# SCH_CapibaraZero_PCB_2024-12-05.net
KiCad netlist of a schematic drawn in EasyEDA
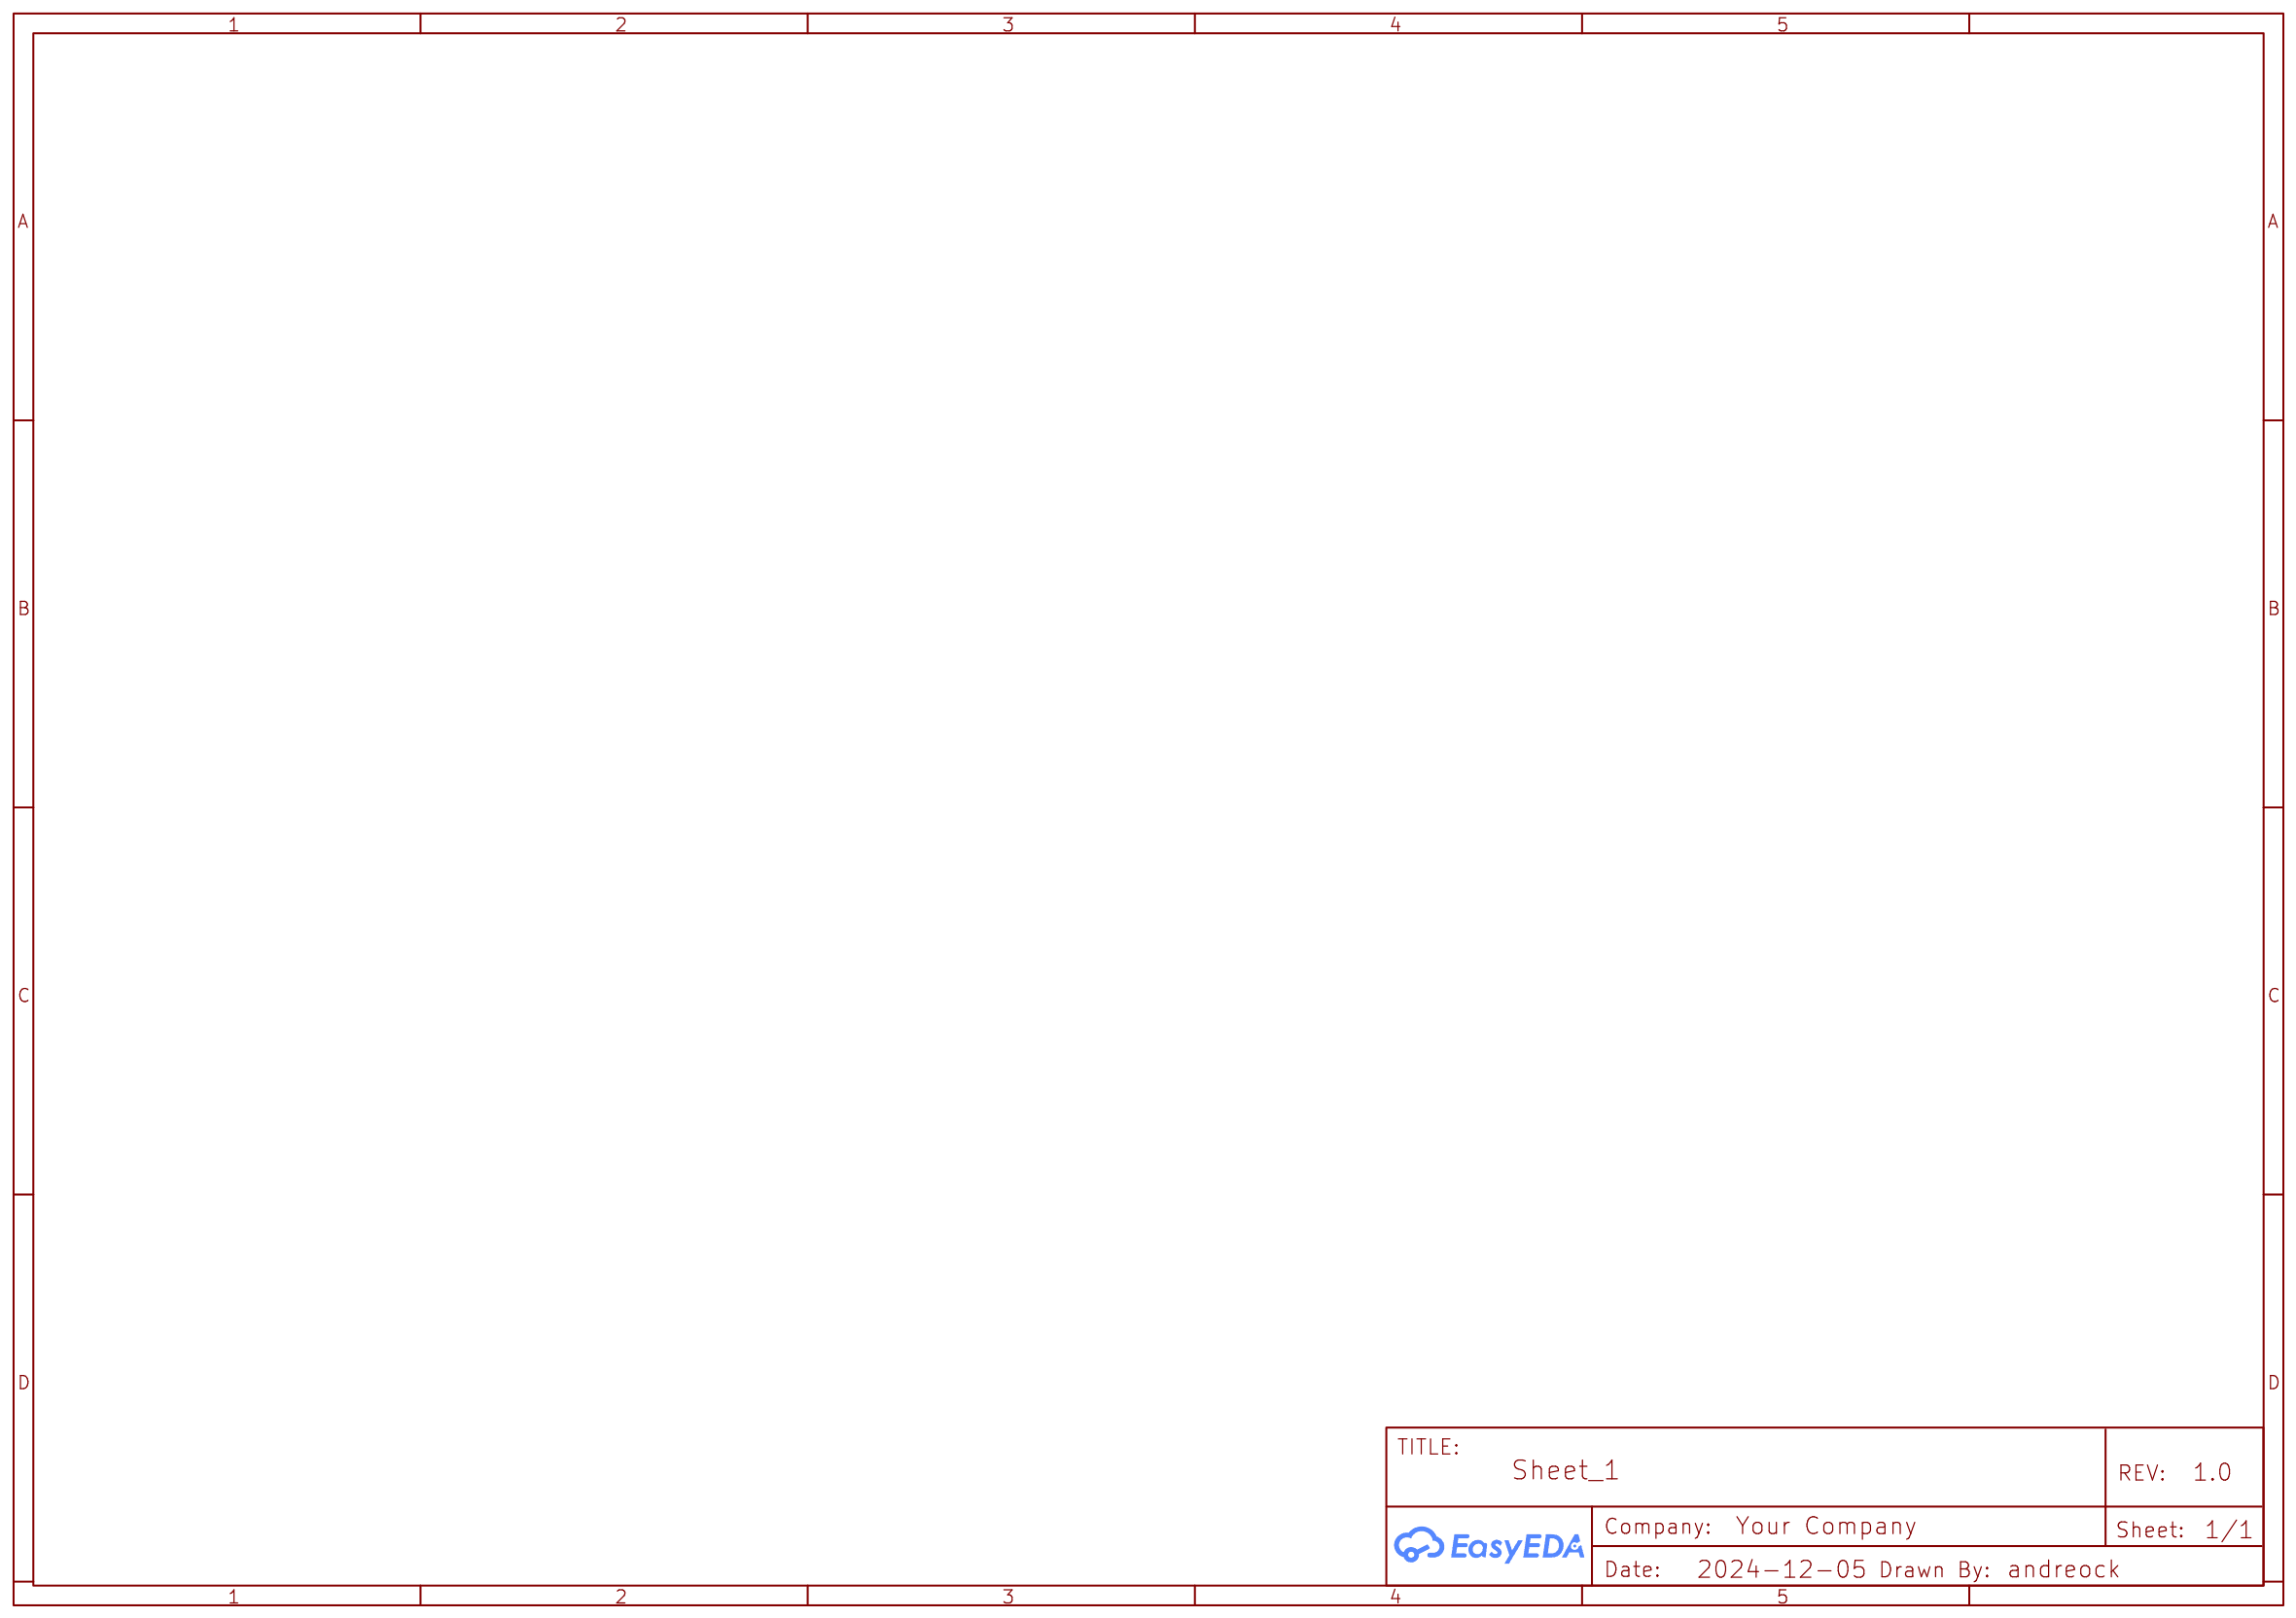
[diagram p0: Sheet_1]
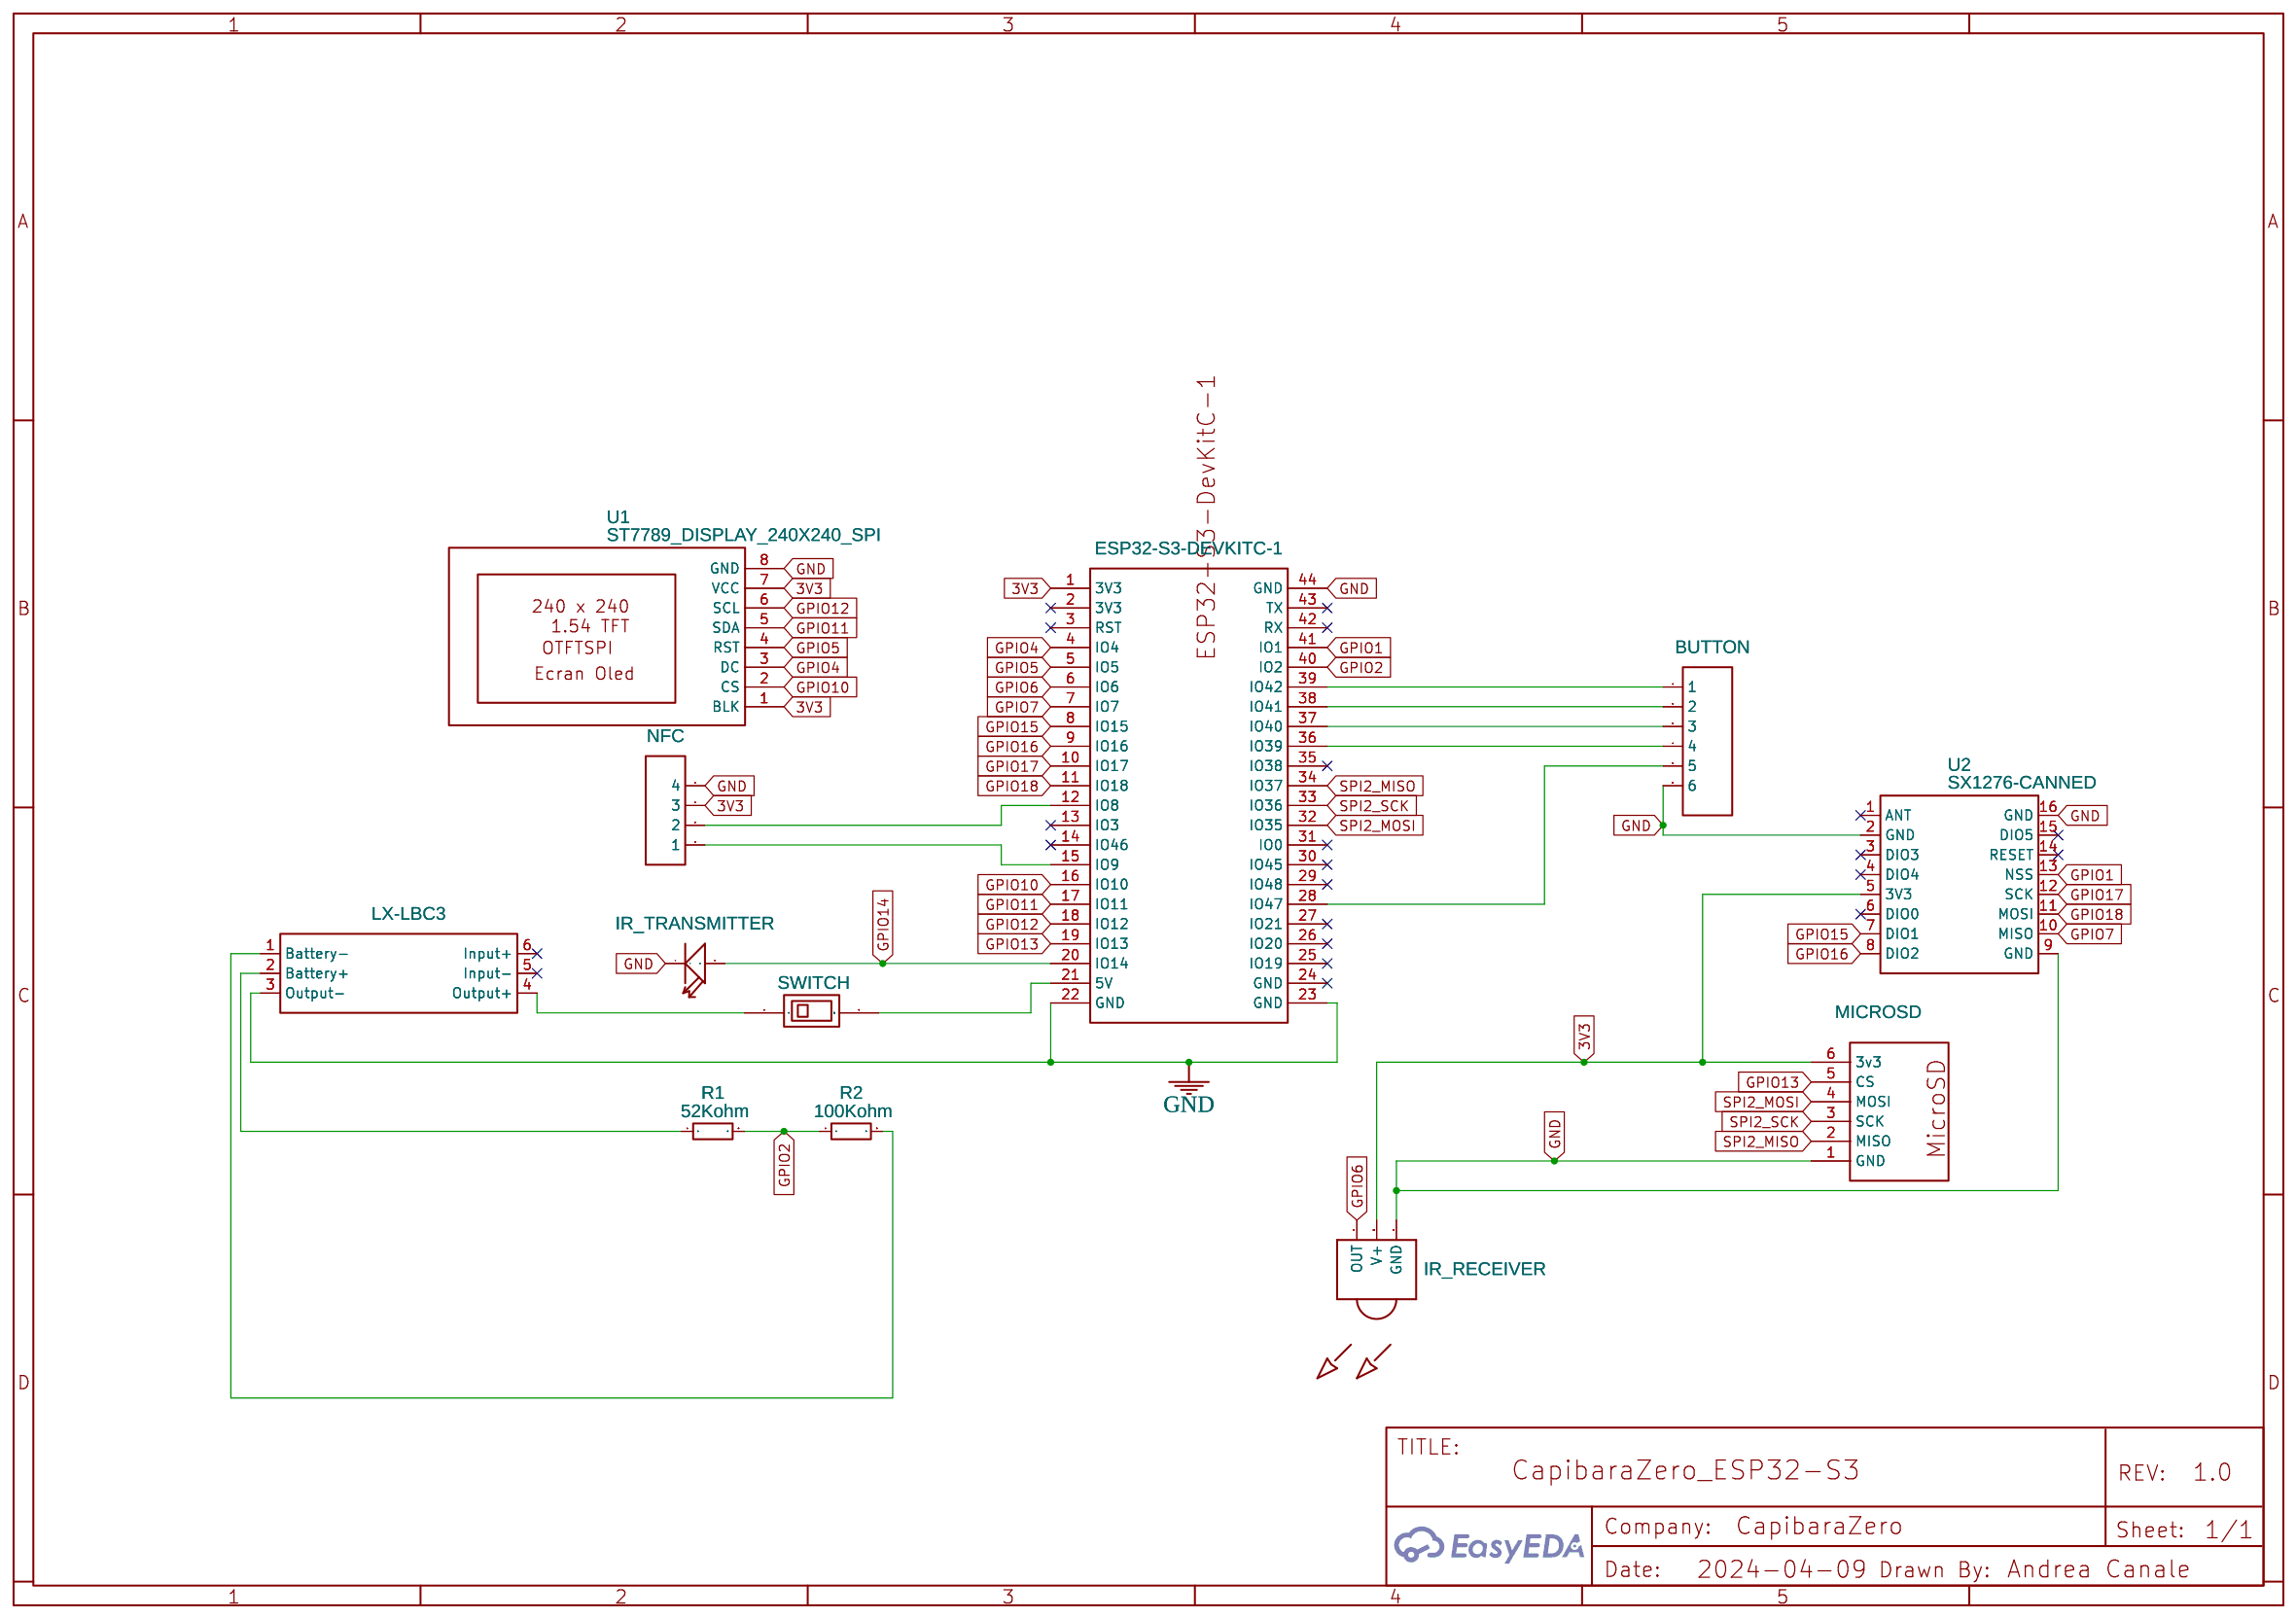
[diagram p1: CapibaraZero_Main_Scheme]
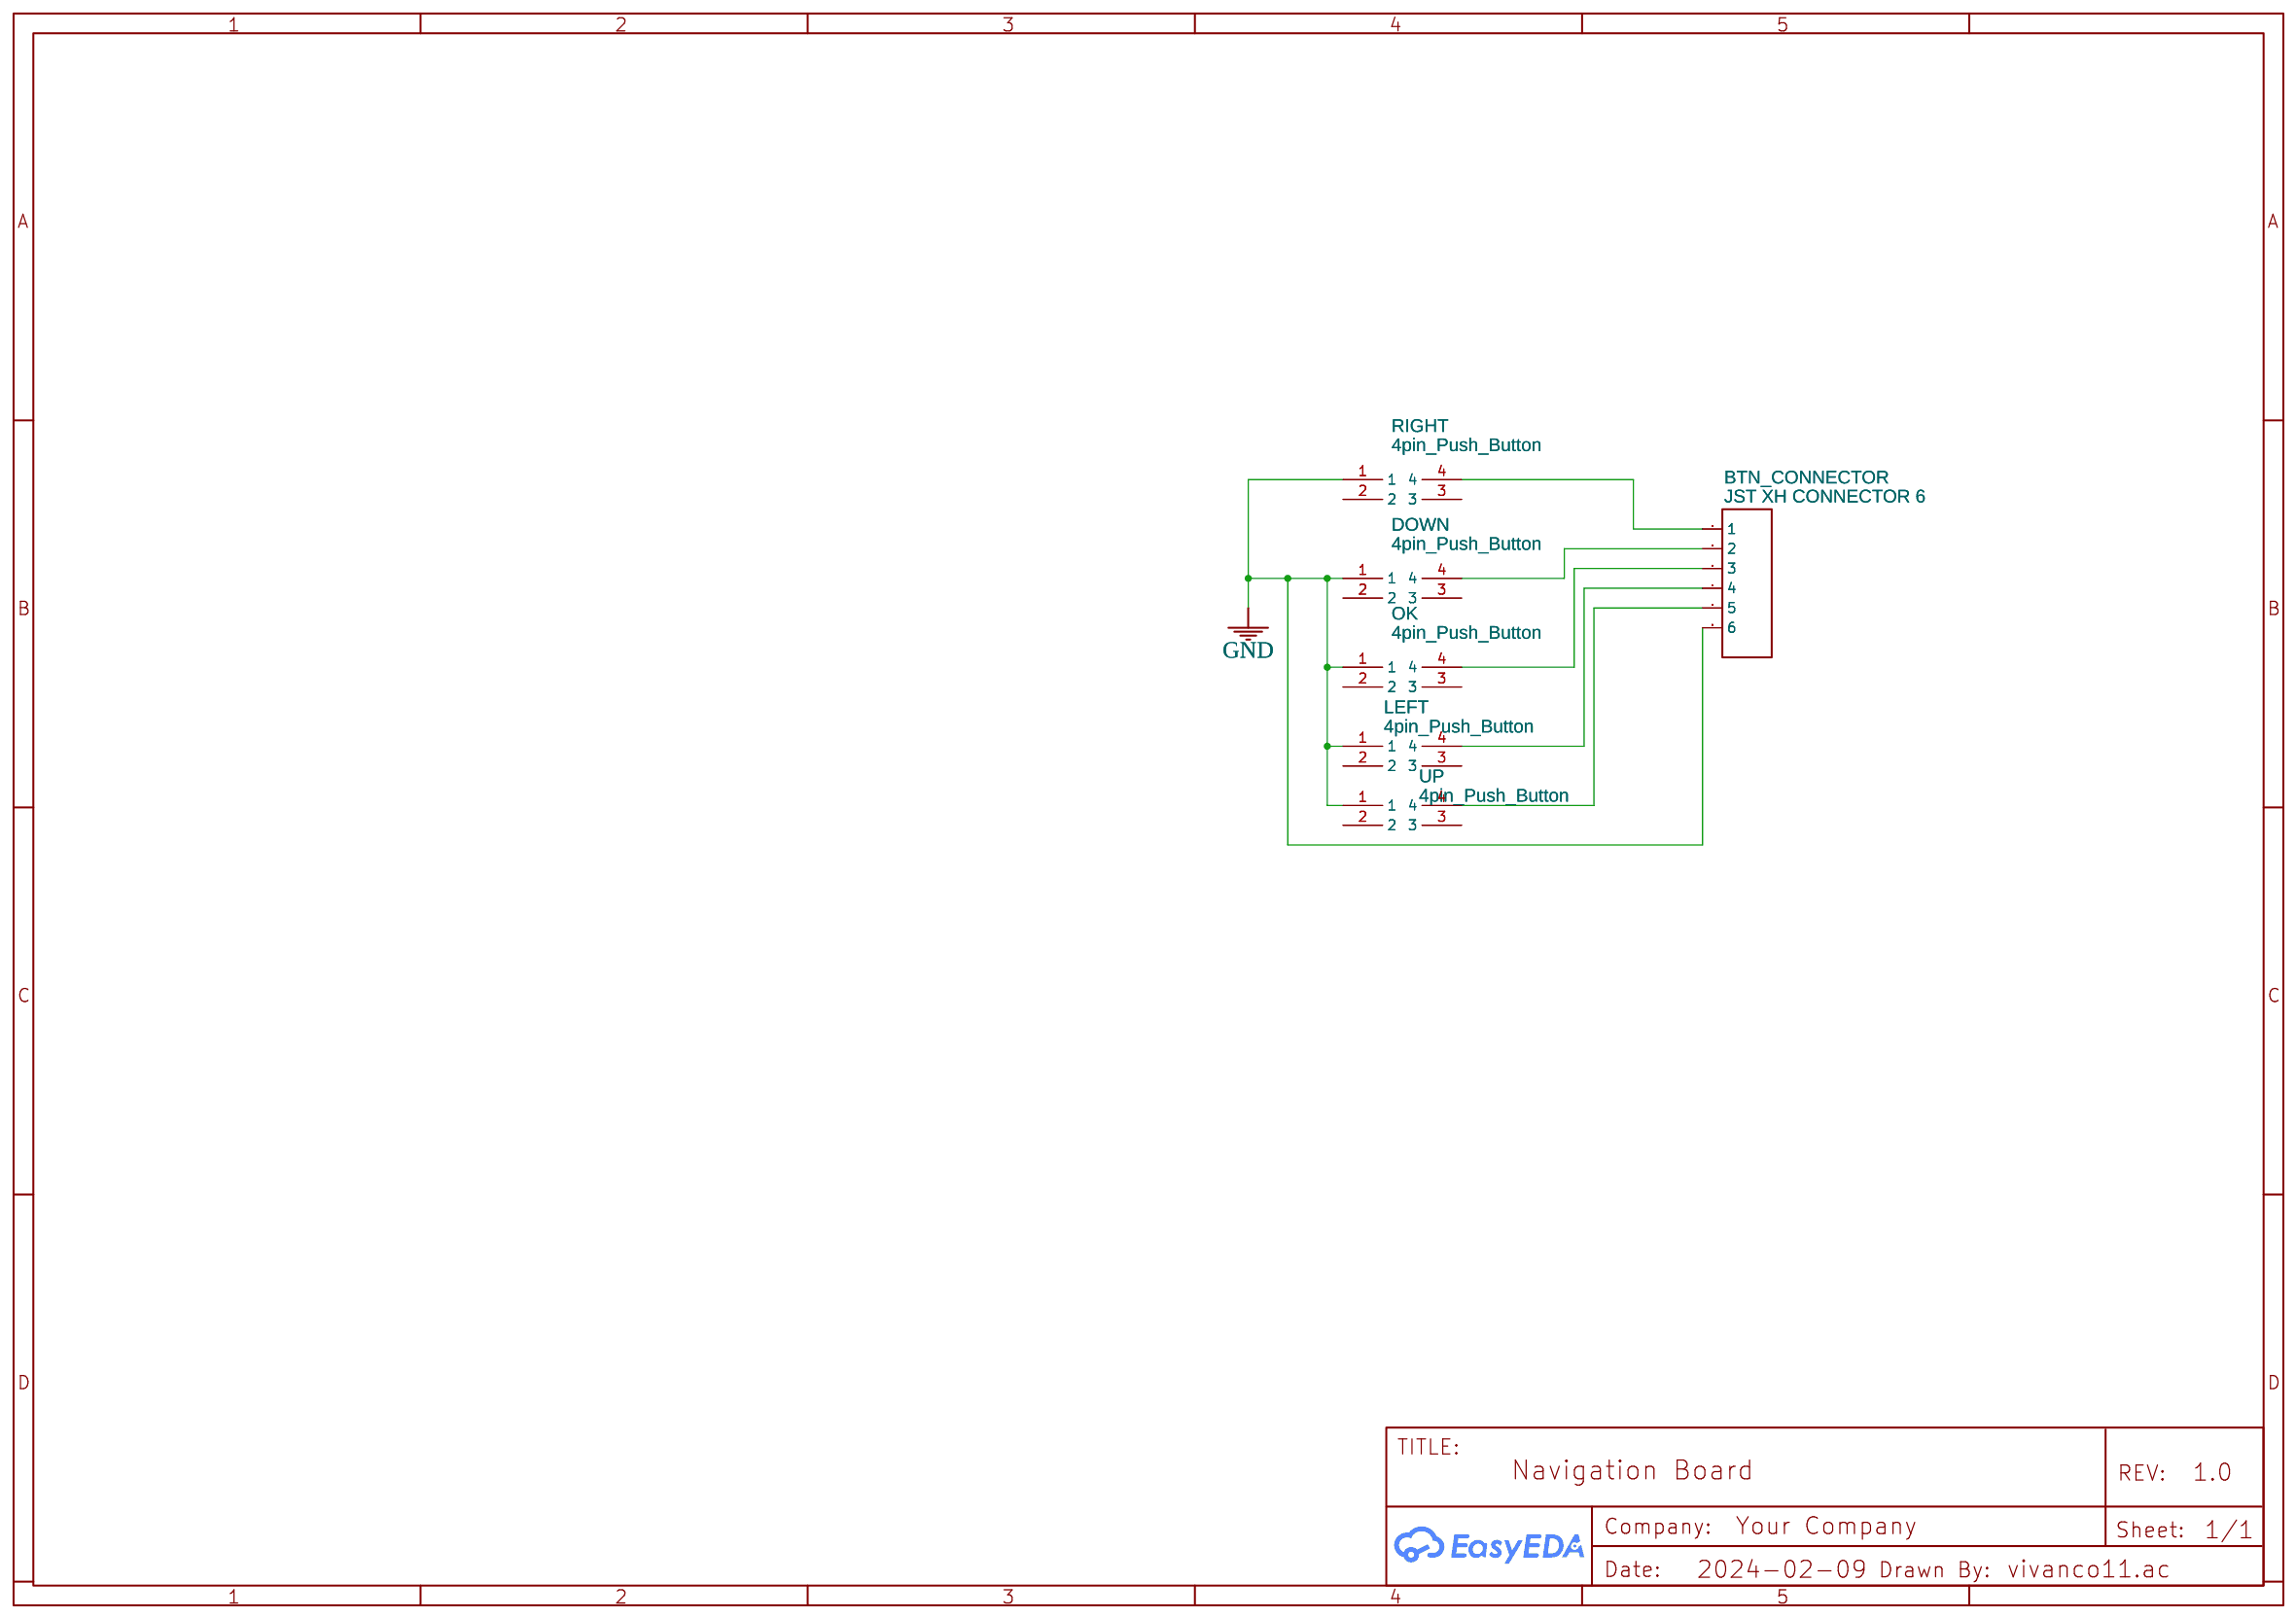
[diagram p2: Navigation board]

(export (version "E")
  (design (tool "Eeschema 10.0.6"))
  (components
    (comp (ref "BUTTON")
      (value "BTN Connector")
      (fields (field (name "Manufacturer Part") "JST_XH CONNECTOR"))
      (libsource (lib "") (part "JST XH CONNECTOR 6"))
    )
    (comp (ref "ESP32-S3-DEVKITC-1")
      (value "ESP32-S3-DevKitC-1 development board")
      (fields (field (name "Manufacturer") "Espressif"))
      (libsource (lib "") (part "ESP32-S3-DevKitC-1 development board"))
    )
    (comp (ref "IR_RECEIVER") (value "IR RECEIVER") (libsource (lib "") (part "IR TRANSMITTER")))
    (comp (ref "IR_TRANSMITTER")
      (value "DIP-IR-LED-940NM(2P-D5MM)")
      (fields (field (name "Manufacturer Part") "IR523B-W60W1"))
      (libsource (lib "") (part "DIP-IR-LED-940NM(2P-D5MM)"))
    )
    (comp (ref "LX-LBC3") (value "LX-LBC3") (libsource (lib "") (part "LX-LBC3")))
    (comp (ref "MICROSD") (value "MicroSDSPI") (libsource (lib "") (part "MicroSDSPI")))
    (comp (ref "NFC")
      (value "NFC Connector")
      (fields (field (name "Manufacturer Part") "JST_XH CONNECTOR"))
      (libsource (lib "") (part "JST XH CONNECTOR 4"))
    )
    (comp (ref "R1")
      (value "52Kohm")
      (fields
        (field (name "Manufacturer Part") "EWWR0001J20R0T9")
        (field (name "Manufacturer") "ResistorToday")
      )
      (libsource (lib "") (part "Resistor Normal"))
    )
    (comp (ref "R2")
      (value "100Kohm")
      (fields
        (field (name "Manufacturer Part") "EWWR0001J20R0T9")
        (field (name "Manufacturer") "ResistorToday")
      )
      (libsource (lib "") (part "Resistor Normal"))
    )
    (comp (ref "SWITCH") (value "1 Pole DIP switch") (libsource (lib "") (part "1 Pole DIP switch")))
    (comp (ref "U1")
      (value "ST7789_DISPLAY_240X240_SPI")
      (libsource (lib "") (part "ST7789_DISPLAY_240X240_SPI"))
    )
    (comp (ref "U2")
      (value "SX1276-CANNED")
      (fields (field (name "Manufacturer Part") "LoRa1276-C1") (field (name "Manufacturer") "G-NiceRF"))
      (libsource (lib "") (part "SX1276-CANNED"))
    )
    (comp (ref "BTN_CONNECTOR")
      (value "JST XH CONNECTOR 6")
      (fields (field (name "Manufacturer Part") "JST_XH CONNECTOR"))
      (libsource (lib "") (part "JST XH CONNECTOR 6"))
    )
    (comp (ref "DOWN") (value "4pin_Push_Button") (libsource (lib "") (part "4pin_Push_Button_3")))
    (comp (ref "LEFT") (value "4pin_Push_Button") (libsource (lib "") (part "4pin_Push_Button")))
    (comp (ref "OK") (value "4pin_Push_Button") (libsource (lib "") (part "4pin_Push_Button_4")))
    (comp (ref "RIGHT") (value "4pin_Push_Button") (libsource (lib "") (part "4pin_Push_Button_2")))
    (comp (ref "UP") (value "4pin_Push_Button") (libsource (lib "") (part "4pin_Push_Button_1")))
  )
  (nets
    (net (code "1") (name "3V3") (class "Default")
      (node (ref "ESP32-S3-DEVKITC-1") (pin "1") (pinfunction "3V3_1") (pintype "unspecified"))
      (node (ref "IR_RECEIVER") (pin "VCC") (pinfunction "V+_VCC") (pintype "unspecified"))
      (node (ref "MICROSD") (pin "6") (pinfunction "3v3_6") (pintype "unspecified"))
      (node (ref "NFC") (pin "3") (pinfunction "3_3") (pintype "unspecified"))
      (node (ref "U1") (pin "1") (pinfunction "BLK_1") (pintype "unspecified"))
      (node (ref "U1") (pin "7") (pinfunction "VCC_7") (pintype "unspecified"))
      (node (ref "U2") (pin "5") (pinfunction "3V3_5") (pintype "unspecified"))
    )
    (net (code "2") (name "GND") (class "Default")
      (node (ref "BTN_CONNECTOR") (pin "6") (pinfunction "6_6") (pintype "unspecified"))
      (node (ref "BUTTON") (pin "6") (pinfunction "6_6") (pintype "unspecified"))
      (node (ref "DOWN") (pin "1") (pinfunction "1_1") (pintype "unspecified"))
      (node (ref "ESP32-S3-DEVKITC-1") (pin "22") (pinfunction "GND_22") (pintype "unspecified"))
      (node (ref "ESP32-S3-DEVKITC-1") (pin "23") (pinfunction "GND_23") (pintype "unspecified"))
      (node (ref "ESP32-S3-DEVKITC-1") (pin "44") (pinfunction "GND_44") (pintype "unspecified"))
      (node (ref "IR_RECEIVER") (pin "GND") (pinfunction "GND_GND") (pintype "unspecified"))
      (node (ref "IR_TRANSMITTER") (pin "-") (pinfunction "-_-") (pintype "unspecified"))
      (node (ref "LEFT") (pin "1") (pinfunction "1_1") (pintype "unspecified"))
      (node (ref "LX-LBC3") (pin "3") (pinfunction "Output-_3") (pintype "unspecified"))
      (node (ref "MICROSD") (pin "1") (pinfunction "GND_1") (pintype "unspecified"))
      (node (ref "NFC") (pin "4") (pinfunction "4_4") (pintype "unspecified"))
      (node (ref "OK") (pin "1") (pinfunction "1_1") (pintype "unspecified"))
      (node (ref "RIGHT") (pin "1") (pinfunction "1_1") (pintype "unspecified"))
      (node (ref "U1") (pin "8") (pinfunction "GND_8") (pintype "unspecified"))
      (node (ref "U2") (pin "16") (pinfunction "GND_16") (pintype "unspecified"))
      (node (ref "U2") (pin "2") (pinfunction "GND_2") (pintype "unspecified"))
      (node (ref "U2") (pin "9") (pinfunction "GND_9") (pintype "unspecified"))
      (node (ref "UP") (pin "1") (pinfunction "1_1") (pintype "unspecified"))
    )
    (net (code "3") (name "GPIO1") (class "Default")
      (node (ref "ESP32-S3-DEVKITC-1") (pin "41") (pinfunction "IO1_41") (pintype "unspecified"))
      (node (ref "U2") (pin "13") (pinfunction "NSS_13") (pintype "unspecified"))
    )
    (net (code "4") (name "GPIO2") (class "Default")
      (node (ref "ESP32-S3-DEVKITC-1") (pin "40") (pinfunction "IO2_40") (pintype "unspecified"))
      (node (ref "R1") (pin "2") (pinfunction "2_2") (pintype "unspecified"))
      (node (ref "R2") (pin "1") (pinfunction "1_1") (pintype "unspecified"))
    )
    (net (code "5") (name "GPIO4") (class "Default")
      (node (ref "ESP32-S3-DEVKITC-1") (pin "4") (pinfunction "IO4_4") (pintype "unspecified"))
      (node (ref "U1") (pin "3") (pinfunction "DC_3") (pintype "unspecified"))
    )
    (net (code "6") (name "GPIO5") (class "Default")
      (node (ref "ESP32-S3-DEVKITC-1") (pin "5") (pinfunction "IO5_5") (pintype "unspecified"))
      (node (ref "U1") (pin "4") (pinfunction "RST_4") (pintype "unspecified"))
    )
    (net (code "7") (name "GPIO6") (class "Default")
      (node (ref "ESP32-S3-DEVKITC-1") (pin "6") (pinfunction "IO6_6") (pintype "unspecified"))
      (node (ref "IR_RECEIVER") (pin "OUT") (pinfunction "OUT_OUT") (pintype "unspecified"))
    )
    (net (code "8") (name "GPIO7") (class "Default")
      (node (ref "ESP32-S3-DEVKITC-1") (pin "7") (pinfunction "IO7_7") (pintype "unspecified"))
      (node (ref "U2") (pin "10") (pinfunction "MISO_10") (pintype "unspecified"))
    )
    (net (code "9") (name "GPIO10") (class "Default")
      (node (ref "ESP32-S3-DEVKITC-1") (pin "16") (pinfunction "IO10_16") (pintype "unspecified"))
      (node (ref "U1") (pin "2") (pinfunction "CS_2") (pintype "unspecified"))
    )
    (net (code "10") (name "GPIO11") (class "Default")
      (node (ref "ESP32-S3-DEVKITC-1") (pin "17") (pinfunction "IO11_17") (pintype "unspecified"))
      (node (ref "U1") (pin "5") (pinfunction "SDA_5") (pintype "unspecified"))
    )
    (net (code "11") (name "GPIO12") (class "Default")
      (node (ref "ESP32-S3-DEVKITC-1") (pin "18") (pinfunction "IO12_18") (pintype "unspecified"))
      (node (ref "U1") (pin "6") (pinfunction "SCL_6") (pintype "unspecified"))
    )
    (net (code "12") (name "GPIO13") (class "Default")
      (node (ref "ESP32-S3-DEVKITC-1") (pin "19") (pinfunction "IO13_19") (pintype "unspecified"))
      (node (ref "MICROSD") (pin "5") (pinfunction "CS_5") (pintype "unspecified"))
    )
    (net (code "13") (name "GPIO14") (class "Default")
      (node (ref "ESP32-S3-DEVKITC-1") (pin "20") (pinfunction "IO14_20") (pintype "unspecified"))
      (node (ref "IR_TRANSMITTER") (pin "+") (pinfunction "+_+") (pintype "unspecified"))
    )
    (net (code "14") (name "GPIO15") (class "Default")
      (node (ref "ESP32-S3-DEVKITC-1") (pin "8") (pinfunction "IO15_8") (pintype "unspecified"))
      (node (ref "U2") (pin "7") (pinfunction "DIO1_7") (pintype "unspecified"))
    )
    (net (code "15") (name "GPIO16") (class "Default")
      (node (ref "ESP32-S3-DEVKITC-1") (pin "9") (pinfunction "IO16_9") (pintype "unspecified"))
      (node (ref "U2") (pin "8") (pinfunction "DIO2_8") (pintype "unspecified"))
    )
    (net (code "16") (name "GPIO17") (class "Default")
      (node (ref "ESP32-S3-DEVKITC-1") (pin "10") (pinfunction "IO17_10") (pintype "unspecified"))
      (node (ref "U2") (pin "12") (pinfunction "SCK_12") (pintype "unspecified"))
    )
    (net (code "17") (name "GPIO18") (class "Default")
      (node (ref "ESP32-S3-DEVKITC-1") (pin "11") (pinfunction "IO18_11") (pintype "unspecified"))
      (node (ref "U2") (pin "11") (pinfunction "MOSI_11") (pintype "unspecified"))
    )
    (net (code "18") (name "Net-(BTN_CONNECTOR-Pad1)") (class "Default")
      (node (ref "BTN_CONNECTOR") (pin "1") (pinfunction "1_1") (pintype "unspecified"))
      (node (ref "RIGHT") (pin "4") (pinfunction "4_4") (pintype "unspecified"))
    )
    (net (code "19") (name "Net-(BTN_CONNECTOR-Pad2)") (class "Default")
      (node (ref "BTN_CONNECTOR") (pin "2") (pinfunction "2_2") (pintype "unspecified"))
      (node (ref "DOWN") (pin "4") (pinfunction "4_4") (pintype "unspecified"))
    )
    (net (code "20") (name "Net-(BTN_CONNECTOR-Pad3)") (class "Default")
      (node (ref "BTN_CONNECTOR") (pin "3") (pinfunction "3_3") (pintype "unspecified"))
      (node (ref "OK") (pin "4") (pinfunction "4_4") (pintype "unspecified"))
    )
    (net (code "21") (name "Net-(BTN_CONNECTOR-Pad4)") (class "Default")
      (node (ref "BTN_CONNECTOR") (pin "4") (pinfunction "4_4") (pintype "unspecified"))
      (node (ref "LEFT") (pin "4") (pinfunction "4_4") (pintype "unspecified"))
    )
    (net (code "22") (name "Net-(BTN_CONNECTOR-Pad5)") (class "Default")
      (node (ref "BTN_CONNECTOR") (pin "5") (pinfunction "5_5") (pintype "unspecified"))
      (node (ref "UP") (pin "4") (pinfunction "4_4") (pintype "unspecified"))
    )
    (net (code "23") (name "Net-(ESP32-S3-DEVKITC-1-5V)") (class "Default")
      (node (ref "ESP32-S3-DEVKITC-1") (pin "21") (pinfunction "5V_21") (pintype "unspecified"))
      (node (ref "SWITCH") (pin "2") (pinfunction "OUT_2") (pintype "unspecified"))
    )
    (net (code "24") (name "Net-(ESP32-S3-DEVKITC-1-IO8)") (class "Default")
      (node (ref "ESP32-S3-DEVKITC-1") (pin "12") (pinfunction "IO8_12") (pintype "unspecified"))
      (node (ref "NFC") (pin "2") (pinfunction "2_2") (pintype "unspecified"))
    )
    (net (code "25") (name "Net-(ESP32-S3-DEVKITC-1-IO9)") (class "Default")
      (node (ref "ESP32-S3-DEVKITC-1") (pin "15") (pinfunction "IO9_15") (pintype "unspecified"))
      (node (ref "NFC") (pin "1") (pinfunction "1_1") (pintype "unspecified"))
    )
    (net (code "26") (name "Net-(ESP32-S3-DEVKITC-1-IO39)") (class "Default")
      (node (ref "BUTTON") (pin "4") (pinfunction "4_4") (pintype "unspecified"))
      (node (ref "ESP32-S3-DEVKITC-1") (pin "36") (pinfunction "IO39_36") (pintype "unspecified"))
    )
    (net (code "27") (name "Net-(ESP32-S3-DEVKITC-1-IO40)") (class "Default")
      (node (ref "BUTTON") (pin "3") (pinfunction "3_3") (pintype "unspecified"))
      (node (ref "ESP32-S3-DEVKITC-1") (pin "37") (pinfunction "IO40_37") (pintype "unspecified"))
    )
    (net (code "28") (name "Net-(ESP32-S3-DEVKITC-1-IO41)") (class "Default")
      (node (ref "BUTTON") (pin "2") (pinfunction "2_2") (pintype "unspecified"))
      (node (ref "ESP32-S3-DEVKITC-1") (pin "38") (pinfunction "IO41_38") (pintype "unspecified"))
    )
    (net (code "29") (name "Net-(ESP32-S3-DEVKITC-1-IO42)") (class "Default")
      (node (ref "BUTTON") (pin "1") (pinfunction "1_1") (pintype "unspecified"))
      (node (ref "ESP32-S3-DEVKITC-1") (pin "39") (pinfunction "IO42_39") (pintype "unspecified"))
    )
    (net (code "30") (name "Net-(ESP32-S3-DEVKITC-1-IO47)") (class "Default")
      (node (ref "BUTTON") (pin "5") (pinfunction "5_5") (pintype "unspecified"))
      (node (ref "ESP32-S3-DEVKITC-1") (pin "28") (pinfunction "IO47_28") (pintype "unspecified"))
    )
    (net (code "31") (name "Net-(LX-LBC3-Battery+)") (class "Default")
      (node (ref "LX-LBC3") (pin "2") (pinfunction "Battery+_2") (pintype "unspecified"))
      (node (ref "R1") (pin "1") (pinfunction "1_1") (pintype "unspecified"))
    )
    (net (code "32") (name "Net-(LX-LBC3-Battery-)") (class "Default")
      (node (ref "LX-LBC3") (pin "1") (pinfunction "Battery-_1") (pintype "unspecified"))
      (node (ref "R2") (pin "2") (pinfunction "2_2") (pintype "unspecified"))
    )
    (net (code "33") (name "Net-(LX-LBC3-Output+)") (class "Default")
      (node (ref "LX-LBC3") (pin "4") (pinfunction "Output+_4") (pintype "unspecified"))
      (node (ref "SWITCH") (pin "1") (pinfunction "IN_1") (pintype "unspecified"))
    )
    (net (code "34") (name "SPI2_MISO") (class "Default")
      (node (ref "ESP32-S3-DEVKITC-1") (pin "34") (pinfunction "IO37_34") (pintype "unspecified"))
      (node (ref "MICROSD") (pin "2") (pinfunction "MISO_2") (pintype "unspecified"))
    )
    (net (code "35") (name "SPI2_MOSI") (class "Default")
      (node (ref "ESP32-S3-DEVKITC-1") (pin "32") (pinfunction "IO35_32") (pintype "unspecified"))
      (node (ref "MICROSD") (pin "4") (pinfunction "MOSI_4") (pintype "unspecified"))
    )
    (net (code "36") (name "SPI2_SCK") (class "Default")
      (node (ref "ESP32-S3-DEVKITC-1") (pin "33") (pinfunction "IO36_33") (pintype "unspecified"))
      (node (ref "MICROSD") (pin "3") (pinfunction "SCK_3") (pintype "unspecified"))
    )
    (net (code "37") (name "unconnected-(DOWN-Pad2)") (class "Default")
      (node (ref "DOWN") (pin "2") (pinfunction "2_2") (pintype "unspecified"))
    )
    (net (code "38") (name "unconnected-(DOWN-Pad3)") (class "Default")
      (node (ref "DOWN") (pin "3") (pinfunction "3_3") (pintype "unspecified"))
    )
    (net (code "39") (name "unconnected-(ESP32-S3-DEVKITC-1-3V3-Pad2)") (class "Default")
      (node (ref "ESP32-S3-DEVKITC-1") (pin "2") (pinfunction "3V3_2") (pintype "unspecified+no_connect"))
    )
    (net (code "40") (name "unconnected-(ESP32-S3-DEVKITC-1-GND-Pad24)") (class "Default")
      (node (ref "ESP32-S3-DEVKITC-1") (pin "24") (pinfunction "GND_24") (pintype "unspecified+no_connect"))
    )
    (net (code "41") (name "unconnected-(ESP32-S3-DEVKITC-1-IO0-Pad31)") (class "Default")
      (node (ref "ESP32-S3-DEVKITC-1") (pin "31") (pinfunction "IO0_31") (pintype "unspecified+no_connect"))
    )
    (net (code "42") (name "unconnected-(ESP32-S3-DEVKITC-1-IO3-Pad13)") (class "Default")
      (node (ref "ESP32-S3-DEVKITC-1") (pin "13") (pinfunction "IO3_13") (pintype "unspecified+no_connect"))
    )
    (net (code "43") (name "unconnected-(ESP32-S3-DEVKITC-1-IO19-Pad25)") (class "Default")
      (node (ref "ESP32-S3-DEVKITC-1") (pin "25") (pinfunction "IO19_25") (pintype "unspecified+no_connect"))
    )
    (net (code "44") (name "unconnected-(ESP32-S3-DEVKITC-1-IO20-Pad26)") (class "Default")
      (node (ref "ESP32-S3-DEVKITC-1") (pin "26") (pinfunction "IO20_26") (pintype "unspecified+no_connect"))
    )
    (net (code "45") (name "unconnected-(ESP32-S3-DEVKITC-1-IO21-Pad27)") (class "Default")
      (node (ref "ESP32-S3-DEVKITC-1") (pin "27") (pinfunction "IO21_27") (pintype "unspecified+no_connect"))
    )
    (net (code "46") (name "unconnected-(ESP32-S3-DEVKITC-1-IO38-Pad35)") (class "Default")
      (node (ref "ESP32-S3-DEVKITC-1") (pin "35") (pinfunction "IO38_35") (pintype "unspecified+no_connect"))
    )
    (net (code "47") (name "unconnected-(ESP32-S3-DEVKITC-1-IO45-Pad30)") (class "Default")
      (node (ref "ESP32-S3-DEVKITC-1") (pin "30") (pinfunction "IO45_30") (pintype "unspecified+no_connect"))
    )
    (net (code "48") (name "unconnected-(ESP32-S3-DEVKITC-1-IO46-Pad14)") (class "Default")
      (node (ref "ESP32-S3-DEVKITC-1") (pin "14") (pinfunction "IO46_14") (pintype "unspecified+no_connect"))
    )
    (net (code "49") (name "unconnected-(ESP32-S3-DEVKITC-1-IO48-Pad29)") (class "Default")
      (node (ref "ESP32-S3-DEVKITC-1") (pin "29") (pinfunction "IO48_29") (pintype "unspecified+no_connect"))
    )
    (net (code "50") (name "unconnected-(ESP32-S3-DEVKITC-1-RST-Pad3)") (class "Default")
      (node (ref "ESP32-S3-DEVKITC-1") (pin "3") (pinfunction "RST_3") (pintype "unspecified+no_connect"))
    )
    (net (code "51") (name "unconnected-(ESP32-S3-DEVKITC-1-RX-Pad42)") (class "Default")
      (node (ref "ESP32-S3-DEVKITC-1") (pin "42") (pinfunction "RX_42") (pintype "unspecified+no_connect"))
    )
    (net (code "52") (name "unconnected-(ESP32-S3-DEVKITC-1-TX-Pad43)") (class "Default")
      (node (ref "ESP32-S3-DEVKITC-1") (pin "43") (pinfunction "TX_43") (pintype "unspecified+no_connect"))
    )
    (net (code "53") (name "unconnected-(LEFT-Pad2)") (class "Default")
      (node (ref "LEFT") (pin "2") (pinfunction "2_2") (pintype "unspecified"))
    )
    (net (code "54") (name "unconnected-(LEFT-Pad3)") (class "Default")
      (node (ref "LEFT") (pin "3") (pinfunction "3_3") (pintype "unspecified"))
    )
    (net (code "55") (name "unconnected-(LX-LBC3-Input+-Pad6)") (class "Default")
      (node (ref "LX-LBC3") (pin "6") (pinfunction "Input+_6") (pintype "unspecified+no_connect"))
    )
    (net (code "56") (name "unconnected-(LX-LBC3-Input--Pad5)") (class "Default")
      (node (ref "LX-LBC3") (pin "5") (pinfunction "Input-_5") (pintype "unspecified+no_connect"))
    )
    (net (code "57") (name "unconnected-(OK-Pad2)") (class "Default")
      (node (ref "OK") (pin "2") (pinfunction "2_2") (pintype "unspecified"))
    )
    (net (code "58") (name "unconnected-(OK-Pad3)") (class "Default")
      (node (ref "OK") (pin "3") (pinfunction "3_3") (pintype "unspecified"))
    )
    (net (code "59") (name "unconnected-(RIGHT-Pad2)") (class "Default")
      (node (ref "RIGHT") (pin "2") (pinfunction "2_2") (pintype "unspecified"))
    )
    (net (code "60") (name "unconnected-(RIGHT-Pad3)") (class "Default")
      (node (ref "RIGHT") (pin "3") (pinfunction "3_3") (pintype "unspecified"))
    )
    (net (code "61") (name "unconnected-(U2-ANT-Pad1)") (class "Default")
      (node (ref "U2") (pin "1") (pinfunction "ANT_1") (pintype "unspecified+no_connect"))
    )
    (net (code "62") (name "unconnected-(U2-DIO0-Pad6)") (class "Default")
      (node (ref "U2") (pin "6") (pinfunction "DIO0_6") (pintype "unspecified+no_connect"))
    )
    (net (code "63") (name "unconnected-(U2-DIO3-Pad3)") (class "Default")
      (node (ref "U2") (pin "3") (pinfunction "DIO3_3") (pintype "unspecified+no_connect"))
    )
    (net (code "64") (name "unconnected-(U2-DIO4-Pad4)") (class "Default")
      (node (ref "U2") (pin "4") (pinfunction "DIO4_4") (pintype "unspecified+no_connect"))
    )
    (net (code "65") (name "unconnected-(U2-DIO5-Pad15)") (class "Default")
      (node (ref "U2") (pin "15") (pinfunction "DIO5_15") (pintype "unspecified+no_connect"))
    )
    (net (code "66") (name "unconnected-(U2-RESET-Pad14)") (class "Default")
      (node (ref "U2") (pin "14") (pinfunction "RESET_14") (pintype "unspecified+no_connect"))
    )
    (net (code "67") (name "unconnected-(UP-Pad2)") (class "Default")
      (node (ref "UP") (pin "2") (pinfunction "2_2") (pintype "unspecified"))
    )
    (net (code "68") (name "unconnected-(UP-Pad3)") (class "Default")
      (node (ref "UP") (pin "3") (pinfunction "3_3") (pintype "unspecified"))
    )
  )
)
